# hd6303-exp-x1.net
KiCad netlist of a schematic drawn in EAGLE
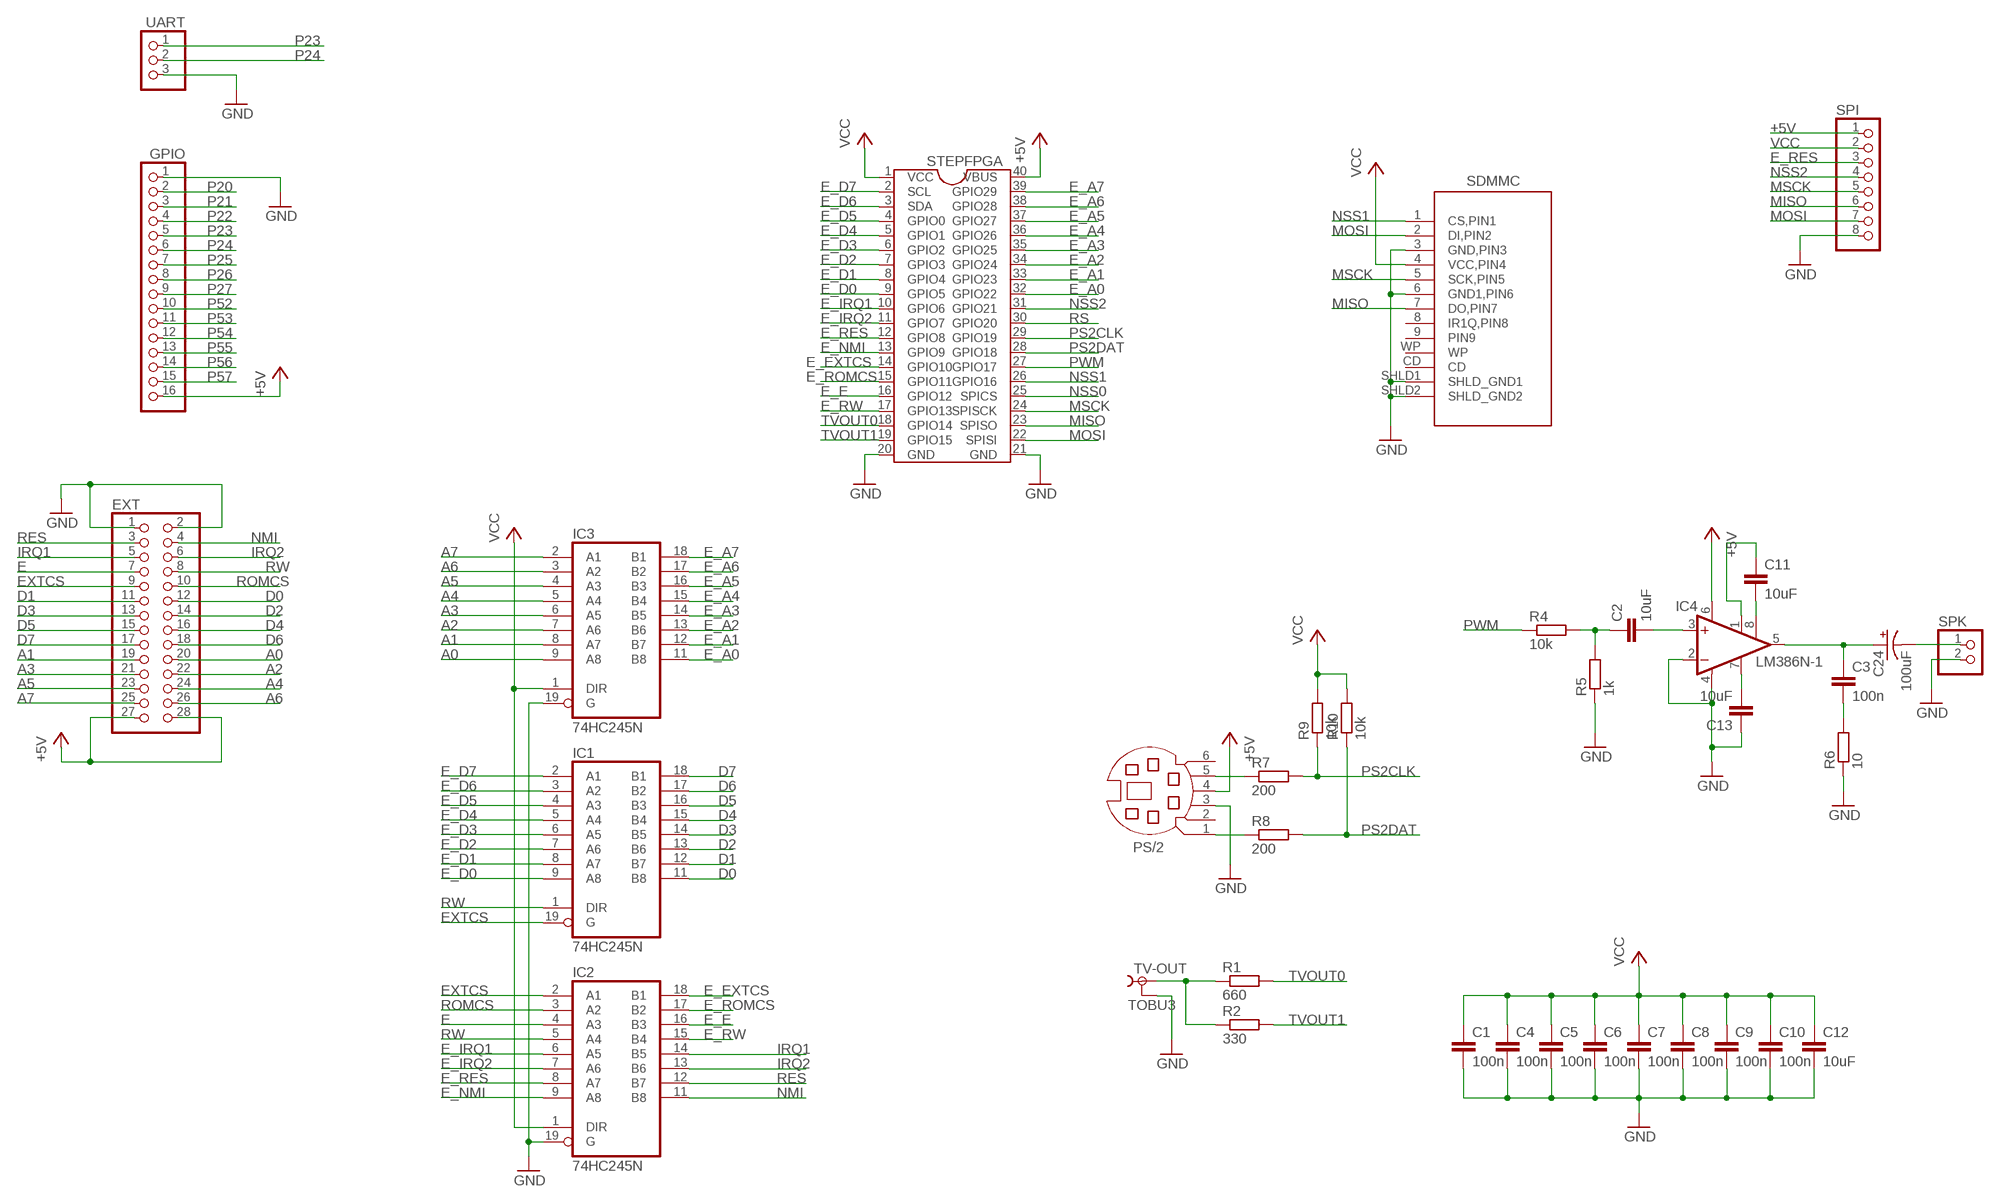
[diagram p0: schematic, sheet 1]
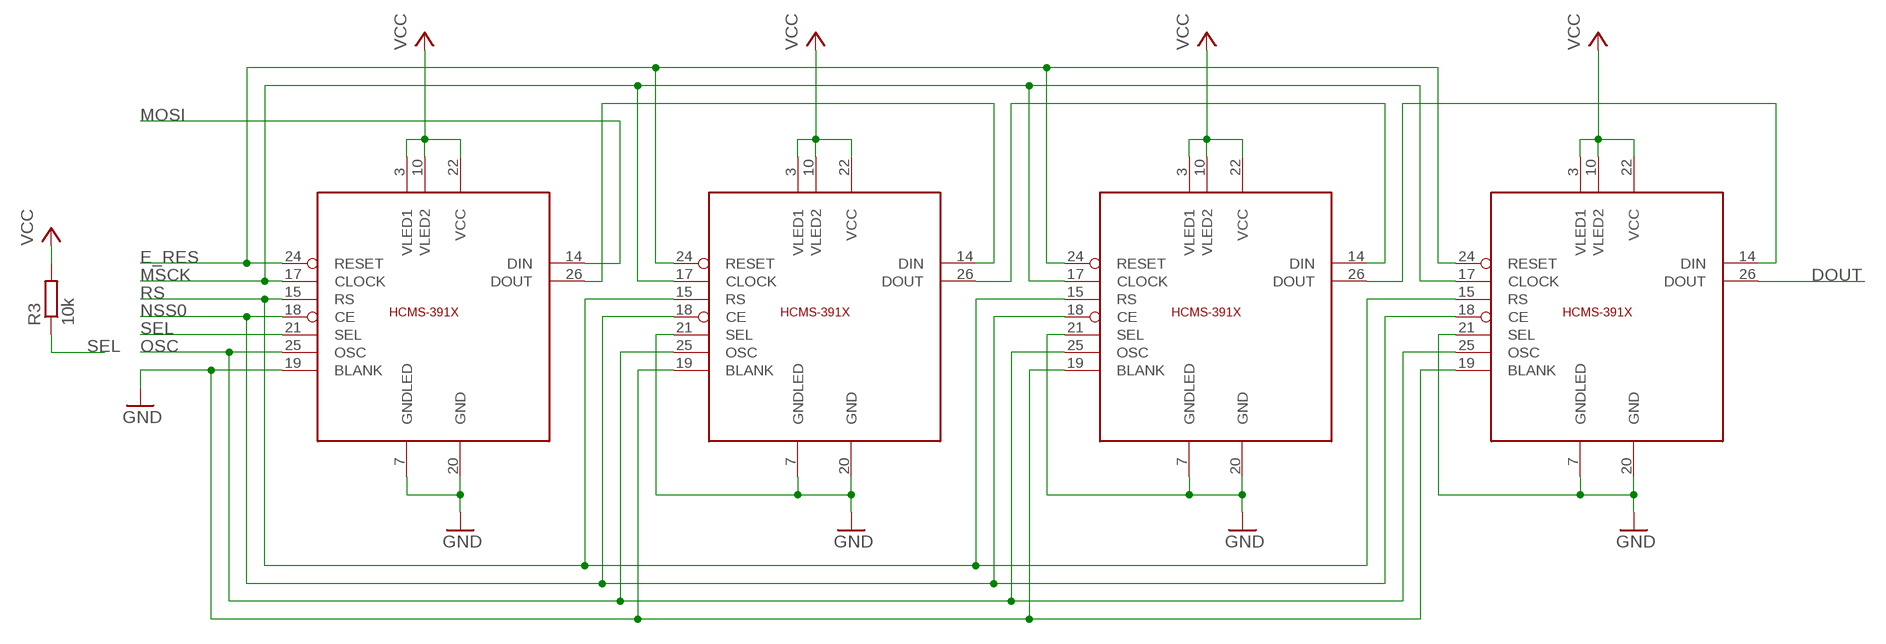
[diagram p1: schematic, sheet 2]

(export (version "E")
  (design (tool "Eeschema 10.0.6"))
  (components
    (comp (ref "R3")
      (value "10k")
      (footprint "eagle-import:R0603")
      (libsource (lib "eagle-import") (part "R-EU_R0603"))
    )
    (comp (ref "U$1")
      (value "HCMS-391X")
      (footprint "eagle-import:HCMS-391X")
      (libsource (lib "eagle-import") (part "HCMS-391X"))
    )
    (comp (ref "U$2")
      (value "HCMS-391X")
      (footprint "eagle-import:HCMS-391X")
      (libsource (lib "eagle-import") (part "HCMS-391X"))
    )
    (comp (ref "U$3")
      (value "HCMS-391X")
      (footprint "eagle-import:HCMS-391X")
      (libsource (lib "eagle-import") (part "HCMS-391X"))
    )
    (comp (ref "U$4")
      (value "HCMS-391X")
      (footprint "eagle-import:HCMS-391X")
      (libsource (lib "eagle-import") (part "HCMS-391X"))
    )
    (comp (ref "C1")
      (value "100n")
      (footprint "eagle-import:C0603")
      (libsource (lib "eagle-import") (part "C-EUC0603"))
    )
    (comp (ref "C2")
      (value "10uF")
      (footprint "eagle-import:C0805")
      (libsource (lib "eagle-import") (part "resistor_348_C-EUC0805"))
    )
    (comp (ref "C3")
      (value "100n")
      (footprint "eagle-import:C0603")
      (libsource (lib "eagle-import") (part "C-EUC0603"))
    )
    (comp (ref "C4")
      (value "100n")
      (footprint "eagle-import:C0603")
      (libsource (lib "eagle-import") (part "C-EUC0603"))
    )
    (comp (ref "C5")
      (value "100n")
      (footprint "eagle-import:C0603")
      (libsource (lib "eagle-import") (part "C-EUC0603"))
    )
    (comp (ref "C6")
      (value "100n")
      (footprint "eagle-import:C0603")
      (libsource (lib "eagle-import") (part "C-EUC0603"))
    )
    (comp (ref "C7")
      (value "100n")
      (footprint "eagle-import:C0603")
      (libsource (lib "eagle-import") (part "C-EUC0603"))
    )
    (comp (ref "C8")
      (value "100n")
      (footprint "eagle-import:C0603")
      (libsource (lib "eagle-import") (part "C-EUC0603"))
    )
    (comp (ref "C9")
      (value "100n")
      (footprint "eagle-import:C0603")
      (libsource (lib "eagle-import") (part "C-EUC0603"))
    )
    (comp (ref "C10")
      (value "100n")
      (footprint "eagle-import:C0603")
      (libsource (lib "eagle-import") (part "C-EUC0603"))
    )
    (comp (ref "C11")
      (value "10uF")
      (footprint "eagle-import:C0805")
      (libsource (lib "eagle-import") (part "resistor_348_C-EUC0805"))
    )
    (comp (ref "C12")
      (value "10uF")
      (footprint "eagle-import:C0805")
      (libsource (lib "eagle-import") (part "resistor_348_C-EUC0805"))
    )
    (comp (ref "C13")
      (value "10uF")
      (footprint "eagle-import:C0805")
      (libsource (lib "eagle-import") (part "resistor_348_C-EUC0805"))
    )
    (comp (ref "C24")
      (value "100uF")
      (footprint "eagle-import:EIA7343")
      (libsource (lib "eagle-import") (part "CAP_POL7343"))
    )
    (comp (ref "EXT")
      (value "PINHD-2X14")
      (footprint "eagle-import:2X14")
      (libsource (lib "eagle-import") (part "PINHD-2X14"))
    )
    (comp (ref "GPIO")
      (value "PINHD-1X16")
      (footprint "eagle-import:1X16")
      (libsource (lib "eagle-import") (part "PINHD-1X16"))
    )
    (comp (ref "IC1")
      (value "74HC245N")
      (footprint "eagle-import:DIL20")
      (libsource (lib "eagle-import") (part "74245NHC"))
    )
    (comp (ref "IC2")
      (value "74HC245N")
      (footprint "eagle-import:DIL20")
      (libsource (lib "eagle-import") (part "74245NHC"))
    )
    (comp (ref "IC3")
      (value "74HC245N")
      (footprint "eagle-import:DIL20")
      (libsource (lib "eagle-import") (part "74245NHC"))
    )
    (comp (ref "IC4")
      (value "LM386N-1")
      (footprint "eagle-import:DIL08")
      (libsource (lib "eagle-import") (part "LM386?-N1"))
    )
    (comp (ref "PS/2")
      (value "MD06SS")
      (footprint "eagle-import:MDIN06SS")
      (libsource (lib "eagle-import") (part "MD06SS"))
    )
    (comp (ref "R1")
      (value "660")
      (footprint "eagle-import:R0603")
      (libsource (lib "eagle-import") (part "R-EU_R0603"))
    )
    (comp (ref "R2")
      (value "330")
      (footprint "eagle-import:R0603")
      (libsource (lib "eagle-import") (part "R-EU_R0603"))
    )
    (comp (ref "R4")
      (value "10k")
      (footprint "eagle-import:R0603")
      (libsource (lib "eagle-import") (part "R-EU_R0603"))
    )
    (comp (ref "R5")
      (value "1k")
      (footprint "eagle-import:R0603")
      (libsource (lib "eagle-import") (part "R-EU_R0603"))
    )
    (comp (ref "R6")
      (value "10")
      (footprint "eagle-import:R0603")
      (libsource (lib "eagle-import") (part "R-EU_R0603"))
    )
    (comp (ref "R7")
      (value "200")
      (footprint "eagle-import:R0603")
      (libsource (lib "eagle-import") (part "R-EU_R0603"))
    )
    (comp (ref "R8")
      (value "200")
      (footprint "eagle-import:R0603")
      (libsource (lib "eagle-import") (part "R-EU_R0603"))
    )
    (comp (ref "R9")
      (value "10k")
      (footprint "eagle-import:R0603")
      (libsource (lib "eagle-import") (part "R-EU_R0603"))
    )
    (comp (ref "R10")
      (value "10k")
      (footprint "eagle-import:R0603")
      (libsource (lib "eagle-import") (part "R-EU_R0603"))
    )
    (comp (ref "SDMMC")
      (value "FCI_SD_SOCKET")
      (footprint "eagle-import:SD-MMC_SOCKET-PP")
      (fields (field (name "MF") "FCI") (field (name "MPN") "10067847-001RLF"))
      (libsource (lib "eagle-import") (part "FCI_SD_SOCKET"))
    )
    (comp (ref "SPI")
      (value "PINHD-1X8")
      (footprint "eagle-import:1X08")
      (libsource (lib "eagle-import") (part "PINHD-1X8"))
    )
    (comp (ref "SPK")
      (value "PINHD-1X2")
      (footprint "eagle-import:1X02")
      (libsource (lib "eagle-import") (part "PINHD-1X2"))
    )
    (comp (ref "STEPFPGA")
      (value "STEPFPGA")
      (footprint "eagle-import:DIL40")
      (libsource (lib "eagle-import") (part "STEPFPGA"))
    )
    (comp (ref "TV-OUT")
      (value "TOBU3")
      (footprint "eagle-import:TOBU3")
      (fields (field (name "MF") "FARNELL") (field (name "MPN") "TOBU 3"))
      (libsource (lib "eagle-import") (part "TOBU3"))
    )
    (comp (ref "UART")
      (value "PINHD-1X3")
      (footprint "eagle-import:1X03")
      (libsource (lib "eagle-import") (part "PINHD-1X3"))
    )
  )
  (nets
    (net (code "1") (name "+5V") (class "Default")
      (node (ref "EXT") (pin "27") (pinfunction "27_27") (pintype "passive"))
      (node (ref "EXT") (pin "28") (pinfunction "28_28") (pintype "passive"))
      (node (ref "GPIO") (pin "16") (pinfunction "16_16") (pintype "passive"))
      (node (ref "IC4") (pin "6") (pinfunction "VS_6") (pintype "power_in"))
      (node (ref "PS/2") (pin "4") (pinfunction "4_4") (pintype "passive"))
      (node (ref "SPI") (pin "1") (pinfunction "1_1") (pintype "passive"))
      (node (ref "STEPFPGA") (pin "40") (pinfunction "VBUS_40") (pintype "power_in"))
    )
    (net (code "2") (name "A0") (class "Default")
      (node (ref "EXT") (pin "20") (pinfunction "20_20") (pintype "passive"))
      (node (ref "IC3") (pin "9") (pinfunction "A8_9") (pintype "bidirectional"))
    )
    (net (code "3") (name "A1") (class "Default")
      (node (ref "EXT") (pin "19") (pinfunction "19_19") (pintype "passive"))
      (node (ref "IC3") (pin "8") (pinfunction "A7_8") (pintype "bidirectional"))
    )
    (net (code "4") (name "A2") (class "Default")
      (node (ref "EXT") (pin "22") (pinfunction "22_22") (pintype "passive"))
      (node (ref "IC3") (pin "7") (pinfunction "A6_7") (pintype "bidirectional"))
    )
    (net (code "5") (name "A3") (class "Default")
      (node (ref "EXT") (pin "21") (pinfunction "21_21") (pintype "passive"))
      (node (ref "IC3") (pin "6") (pinfunction "A5_6") (pintype "bidirectional"))
    )
    (net (code "6") (name "A4") (class "Default")
      (node (ref "EXT") (pin "24") (pinfunction "24_24") (pintype "passive"))
      (node (ref "IC3") (pin "5") (pinfunction "A4_5") (pintype "bidirectional"))
    )
    (net (code "7") (name "A5") (class "Default")
      (node (ref "EXT") (pin "23") (pinfunction "23_23") (pintype "passive"))
      (node (ref "IC3") (pin "4") (pinfunction "A3_4") (pintype "bidirectional"))
    )
    (net (code "8") (name "A6") (class "Default")
      (node (ref "EXT") (pin "26") (pinfunction "26_26") (pintype "passive"))
      (node (ref "IC3") (pin "3") (pinfunction "A2_3") (pintype "bidirectional"))
    )
    (net (code "9") (name "A7") (class "Default")
      (node (ref "EXT") (pin "25") (pinfunction "25_25") (pintype "passive"))
      (node (ref "IC3") (pin "2") (pinfunction "A1_2") (pintype "bidirectional"))
    )
    (net (code "10") (name "D0") (class "Default")
      (node (ref "EXT") (pin "12") (pinfunction "12_12") (pintype "passive"))
      (node (ref "IC1") (pin "11") (pinfunction "B8_11") (pintype "bidirectional"))
    )
    (net (code "11") (name "D1") (class "Default")
      (node (ref "EXT") (pin "11") (pinfunction "11_11") (pintype "passive"))
      (node (ref "IC1") (pin "12") (pinfunction "B7_12") (pintype "bidirectional"))
    )
    (net (code "12") (name "D2") (class "Default")
      (node (ref "EXT") (pin "14") (pinfunction "14_14") (pintype "passive"))
      (node (ref "IC1") (pin "13") (pinfunction "B6_13") (pintype "bidirectional"))
    )
    (net (code "13") (name "D3") (class "Default")
      (node (ref "EXT") (pin "13") (pinfunction "13_13") (pintype "passive"))
      (node (ref "IC1") (pin "14") (pinfunction "B5_14") (pintype "bidirectional"))
    )
    (net (code "14") (name "D4") (class "Default")
      (node (ref "EXT") (pin "16") (pinfunction "16_16") (pintype "passive"))
      (node (ref "IC1") (pin "15") (pinfunction "B4_15") (pintype "bidirectional"))
    )
    (net (code "15") (name "D5") (class "Default")
      (node (ref "EXT") (pin "15") (pinfunction "15_15") (pintype "passive"))
      (node (ref "IC1") (pin "16") (pinfunction "B3_16") (pintype "bidirectional"))
    )
    (net (code "16") (name "D6") (class "Default")
      (node (ref "EXT") (pin "18") (pinfunction "18_18") (pintype "passive"))
      (node (ref "IC1") (pin "17") (pinfunction "B2_17") (pintype "bidirectional"))
    )
    (net (code "17") (name "D7") (class "Default")
      (node (ref "EXT") (pin "17") (pinfunction "17_17") (pintype "passive"))
      (node (ref "IC1") (pin "18") (pinfunction "B1_18") (pintype "bidirectional"))
    )
    (net (code "18") (name "DOUT") (class "Default")
      (node (ref "U$4") (pin "26") (pinfunction "DOUT_26") (pintype "output"))
    )
    (net (code "19") (name "E") (class "Default")
      (node (ref "EXT") (pin "7") (pinfunction "7_7") (pintype "passive"))
      (node (ref "IC2") (pin "4") (pinfunction "A3_4") (pintype "bidirectional"))
    )
    (net (code "20") (name "EXTCS") (class "Default")
      (node (ref "EXT") (pin "9") (pinfunction "9_9") (pintype "passive"))
      (node (ref "IC1") (pin "19") (pinfunction "G_19") (pintype "input"))
      (node (ref "IC2") (pin "2") (pinfunction "A1_2") (pintype "bidirectional"))
    )
    (net (code "21") (name "E_A0") (class "Default")
      (node (ref "IC3") (pin "11") (pinfunction "B8_11") (pintype "bidirectional"))
      (node (ref "STEPFPGA") (pin "32") (pinfunction "GPIO22_32") (pintype "bidirectional"))
    )
    (net (code "22") (name "E_A1") (class "Default")
      (node (ref "IC3") (pin "12") (pinfunction "B7_12") (pintype "bidirectional"))
      (node (ref "STEPFPGA") (pin "33") (pinfunction "GPIO23_33") (pintype "bidirectional"))
    )
    (net (code "23") (name "E_A2") (class "Default")
      (node (ref "IC3") (pin "13") (pinfunction "B6_13") (pintype "bidirectional"))
      (node (ref "STEPFPGA") (pin "34") (pinfunction "GPIO24_34") (pintype "bidirectional"))
    )
    (net (code "24") (name "E_A3") (class "Default")
      (node (ref "IC3") (pin "14") (pinfunction "B5_14") (pintype "bidirectional"))
      (node (ref "STEPFPGA") (pin "35") (pinfunction "GPIO25_35") (pintype "bidirectional"))
    )
    (net (code "25") (name "E_A4") (class "Default")
      (node (ref "IC3") (pin "15") (pinfunction "B4_15") (pintype "bidirectional"))
      (node (ref "STEPFPGA") (pin "36") (pinfunction "GPIO26_36") (pintype "bidirectional"))
    )
    (net (code "26") (name "E_A5") (class "Default")
      (node (ref "IC3") (pin "16") (pinfunction "B3_16") (pintype "bidirectional"))
      (node (ref "STEPFPGA") (pin "37") (pinfunction "GPIO27_37") (pintype "bidirectional"))
    )
    (net (code "27") (name "E_A6") (class "Default")
      (node (ref "IC3") (pin "17") (pinfunction "B2_17") (pintype "bidirectional"))
      (node (ref "STEPFPGA") (pin "38") (pinfunction "GPIO28_38") (pintype "bidirectional"))
    )
    (net (code "28") (name "E_A7") (class "Default")
      (node (ref "IC3") (pin "18") (pinfunction "B1_18") (pintype "bidirectional"))
      (node (ref "STEPFPGA") (pin "39") (pinfunction "GPIO29_39") (pintype "bidirectional"))
    )
    (net (code "29") (name "E_D0") (class "Default")
      (node (ref "IC1") (pin "9") (pinfunction "A8_9") (pintype "bidirectional"))
      (node (ref "STEPFPGA") (pin "9") (pinfunction "GPIO5_9") (pintype "bidirectional"))
    )
    (net (code "30") (name "E_D1") (class "Default")
      (node (ref "IC1") (pin "8") (pinfunction "A7_8") (pintype "bidirectional"))
      (node (ref "STEPFPGA") (pin "8") (pinfunction "GPIO4_8") (pintype "bidirectional"))
    )
    (net (code "31") (name "E_D2") (class "Default")
      (node (ref "IC1") (pin "7") (pinfunction "A6_7") (pintype "bidirectional"))
      (node (ref "STEPFPGA") (pin "7") (pinfunction "GPIO3_7") (pintype "bidirectional"))
    )
    (net (code "32") (name "E_D3") (class "Default")
      (node (ref "IC1") (pin "6") (pinfunction "A5_6") (pintype "bidirectional"))
      (node (ref "STEPFPGA") (pin "6") (pinfunction "GPIO2_6") (pintype "bidirectional"))
    )
    (net (code "33") (name "E_D4") (class "Default")
      (node (ref "IC1") (pin "5") (pinfunction "A4_5") (pintype "bidirectional"))
      (node (ref "STEPFPGA") (pin "5") (pinfunction "GPIO1_5") (pintype "bidirectional"))
    )
    (net (code "34") (name "E_D5") (class "Default")
      (node (ref "IC1") (pin "4") (pinfunction "A3_4") (pintype "bidirectional"))
      (node (ref "STEPFPGA") (pin "4") (pinfunction "GPIO0_4") (pintype "bidirectional"))
    )
    (net (code "35") (name "E_D6") (class "Default")
      (node (ref "IC1") (pin "3") (pinfunction "A2_3") (pintype "bidirectional"))
      (node (ref "STEPFPGA") (pin "3") (pinfunction "SDA_3") (pintype "bidirectional"))
    )
    (net (code "36") (name "E_D7") (class "Default")
      (node (ref "IC1") (pin "2") (pinfunction "A1_2") (pintype "bidirectional"))
      (node (ref "STEPFPGA") (pin "2") (pinfunction "SCL_2") (pintype "bidirectional"))
    )
    (net (code "37") (name "E_E") (class "Default")
      (node (ref "IC2") (pin "16") (pinfunction "B3_16") (pintype "bidirectional"))
      (node (ref "STEPFPGA") (pin "16") (pinfunction "GPIO12_16") (pintype "bidirectional"))
    )
    (net (code "38") (name "E_EXTCS") (class "Default")
      (node (ref "IC2") (pin "18") (pinfunction "B1_18") (pintype "bidirectional"))
      (node (ref "STEPFPGA") (pin "14") (pinfunction "GPIO10_14") (pintype "bidirectional"))
    )
    (net (code "39") (name "E_IRQ1") (class "Default")
      (node (ref "IC2") (pin "6") (pinfunction "A5_6") (pintype "bidirectional"))
      (node (ref "STEPFPGA") (pin "10") (pinfunction "GPIO6_10") (pintype "bidirectional"))
    )
    (net (code "40") (name "E_IRQ2") (class "Default")
      (node (ref "IC2") (pin "7") (pinfunction "A6_7") (pintype "bidirectional"))
      (node (ref "STEPFPGA") (pin "11") (pinfunction "GPIO7_11") (pintype "bidirectional"))
    )
    (net (code "41") (name "E_NMI") (class "Default")
      (node (ref "IC2") (pin "9") (pinfunction "A8_9") (pintype "bidirectional"))
      (node (ref "STEPFPGA") (pin "13") (pinfunction "GPIO9_13") (pintype "bidirectional"))
    )
    (net (code "42") (name "E_RES") (class "Default")
      (node (ref "IC2") (pin "8") (pinfunction "A7_8") (pintype "bidirectional"))
      (node (ref "SPI") (pin "3") (pinfunction "3_3") (pintype "passive"))
      (node (ref "STEPFPGA") (pin "12") (pinfunction "GPIO8_12") (pintype "bidirectional"))
      (node (ref "U$1") (pin "24") (pinfunction "RESET_24") (pintype "input"))
      (node (ref "U$2") (pin "24") (pinfunction "RESET_24") (pintype "input"))
      (node (ref "U$3") (pin "24") (pinfunction "RESET_24") (pintype "input"))
      (node (ref "U$4") (pin "24") (pinfunction "RESET_24") (pintype "input"))
    )
    (net (code "43") (name "E_ROMCS") (class "Default")
      (node (ref "IC2") (pin "17") (pinfunction "B2_17") (pintype "bidirectional"))
      (node (ref "STEPFPGA") (pin "15") (pinfunction "GPIO11_15") (pintype "bidirectional"))
    )
    (net (code "44") (name "E_RW") (class "Default")
      (node (ref "IC2") (pin "15") (pinfunction "B4_15") (pintype "bidirectional"))
      (node (ref "STEPFPGA") (pin "17") (pinfunction "GPIO13_17") (pintype "bidirectional"))
    )
    (net (code "45") (name "GND") (class "Default")
      (node (ref "C1") (pin "2") (pinfunction "2_2") (pintype "passive"))
      (node (ref "C10") (pin "2") (pinfunction "2_2") (pintype "passive"))
      (node (ref "C12") (pin "2") (pinfunction "2_2") (pintype "passive"))
      (node (ref "C13") (pin "1") (pinfunction "1_1") (pintype "passive"))
      (node (ref "C4") (pin "2") (pinfunction "2_2") (pintype "passive"))
      (node (ref "C5") (pin "2") (pinfunction "2_2") (pintype "passive"))
      (node (ref "C6") (pin "2") (pinfunction "2_2") (pintype "passive"))
      (node (ref "C7") (pin "2") (pinfunction "2_2") (pintype "passive"))
      (node (ref "C8") (pin "2") (pinfunction "2_2") (pintype "passive"))
      (node (ref "C9") (pin "2") (pinfunction "2_2") (pintype "passive"))
      (node (ref "EXT") (pin "1") (pinfunction "1_1") (pintype "passive"))
      (node (ref "EXT") (pin "2") (pinfunction "2_2") (pintype "passive"))
      (node (ref "GPIO") (pin "1") (pinfunction "1_1") (pintype "passive"))
      (node (ref "IC2") (pin "19") (pinfunction "G_19") (pintype "input"))
      (node (ref "IC3") (pin "19") (pinfunction "G_19") (pintype "input"))
      (node (ref "IC4") (pin "2") (pinfunction "-IN_2") (pintype "input"))
      (node (ref "IC4") (pin "4") (pinfunction "GND_4") (pintype "power_in"))
      (node (ref "PS/2") (pin "3") (pinfunction "3_3") (pintype "passive"))
      (node (ref "R5") (pin "1") (pinfunction "1_1") (pintype "passive"))
      (node (ref "R6") (pin "1") (pinfunction "1_1") (pintype "passive"))
      (node (ref "SDMMC") (pin "3") (pinfunction "GND,PIN3_3") (pintype "bidirectional"))
      (node (ref "SDMMC") (pin "6") (pinfunction "GND1,PIN6_6") (pintype "bidirectional"))
      (node (ref "SDMMC") (pin "SHLD1") (pinfunction "SHLD_GND1_SHLD1") (pintype "bidirectional"))
      (node (ref "SDMMC") (pin "SHLD2") (pinfunction "SHLD_GND2_SHLD2") (pintype "bidirectional"))
      (node (ref "SPI") (pin "8") (pinfunction "8_8") (pintype "passive"))
      (node (ref "SPK") (pin "2") (pinfunction "2_2") (pintype "passive"))
      (node (ref "STEPFPGA") (pin "20") (pinfunction "GND_20") (pintype "power_in"))
      (node (ref "STEPFPGA") (pin "21") (pinfunction "GND_21") (pintype "power_in"))
      (node (ref "TV-OUT") (pin "2") (pinfunction "2_2") (pintype "passive"))
      (node (ref "TV-OUT") (pin "2@1") (pinfunction "2_2@1") (pintype "passive"))
      (node (ref "TV-OUT") (pin "2@2") (pinfunction "2_2@2") (pintype "passive"))
      (node (ref "U$1") (pin "19") (pinfunction "BLANK_19") (pintype "input"))
      (node (ref "U$1") (pin "20") (pinfunction "GND_20") (pintype "power_in"))
      (node (ref "U$1") (pin "7") (pinfunction "GNDLED_7") (pintype "power_in"))
      (node (ref "U$2") (pin "19") (pinfunction "BLANK_19") (pintype "input"))
      (node (ref "U$2") (pin "20") (pinfunction "GND_20") (pintype "power_in"))
      (node (ref "U$2") (pin "21") (pinfunction "SEL_21") (pintype "input"))
      (node (ref "U$2") (pin "7") (pinfunction "GNDLED_7") (pintype "power_in"))
      (node (ref "U$3") (pin "19") (pinfunction "BLANK_19") (pintype "input"))
      (node (ref "U$3") (pin "20") (pinfunction "GND_20") (pintype "power_in"))
      (node (ref "U$3") (pin "21") (pinfunction "SEL_21") (pintype "input"))
      (node (ref "U$3") (pin "7") (pinfunction "GNDLED_7") (pintype "power_in"))
      (node (ref "U$4") (pin "19") (pinfunction "BLANK_19") (pintype "input"))
      (node (ref "U$4") (pin "20") (pinfunction "GND_20") (pintype "power_in"))
      (node (ref "U$4") (pin "21") (pinfunction "SEL_21") (pintype "input"))
      (node (ref "U$4") (pin "7") (pinfunction "GNDLED_7") (pintype "power_in"))
      (node (ref "UART") (pin "3") (pinfunction "3_3") (pintype "passive"))
    )
    (net (code "46") (name "IRQ1") (class "Default")
      (node (ref "EXT") (pin "5") (pinfunction "5_5") (pintype "passive"))
      (node (ref "IC2") (pin "14") (pinfunction "B5_14") (pintype "bidirectional"))
    )
    (net (code "47") (name "IRQ2") (class "Default")
      (node (ref "EXT") (pin "6") (pinfunction "6_6") (pintype "passive"))
      (node (ref "IC2") (pin "13") (pinfunction "B6_13") (pintype "bidirectional"))
    )
    (net (code "48") (name "MISO") (class "Default")
      (node (ref "SDMMC") (pin "7") (pinfunction "DO,PIN7_7") (pintype "bidirectional"))
      (node (ref "SPI") (pin "6") (pinfunction "6_6") (pintype "passive"))
      (node (ref "STEPFPGA") (pin "23") (pinfunction "SPISO_23") (pintype "bidirectional"))
    )
    (net (code "49") (name "MOSI") (class "Default")
      (node (ref "SDMMC") (pin "2") (pinfunction "DI,PIN2_2") (pintype "bidirectional"))
      (node (ref "SPI") (pin "7") (pinfunction "7_7") (pintype "passive"))
      (node (ref "STEPFPGA") (pin "22") (pinfunction "SPISI_22") (pintype "bidirectional"))
      (node (ref "U$1") (pin "14") (pinfunction "DIN_14") (pintype "input"))
    )
    (net (code "50") (name "MSCK") (class "Default")
      (node (ref "SDMMC") (pin "5") (pinfunction "SCK,PIN5_5") (pintype "bidirectional"))
      (node (ref "SPI") (pin "5") (pinfunction "5_5") (pintype "passive"))
      (node (ref "STEPFPGA") (pin "24") (pinfunction "SPISCK_24") (pintype "bidirectional"))
      (node (ref "U$1") (pin "17") (pinfunction "CLOCK_17") (pintype "input"))
      (node (ref "U$2") (pin "17") (pinfunction "CLOCK_17") (pintype "input"))
      (node (ref "U$3") (pin "17") (pinfunction "CLOCK_17") (pintype "input"))
      (node (ref "U$4") (pin "17") (pinfunction "CLOCK_17") (pintype "input"))
    )
    (net (code "51") (name "NMI") (class "Default")
      (node (ref "EXT") (pin "4") (pinfunction "4_4") (pintype "passive"))
      (node (ref "IC2") (pin "11") (pinfunction "B8_11") (pintype "bidirectional"))
    )
    (net (code "52") (name "NSS0") (class "Default")
      (node (ref "STEPFPGA") (pin "25") (pinfunction "SPICS_25") (pintype "bidirectional"))
      (node (ref "U$1") (pin "18") (pinfunction "CE_18") (pintype "input"))
      (node (ref "U$2") (pin "18") (pinfunction "CE_18") (pintype "input"))
      (node (ref "U$3") (pin "18") (pinfunction "CE_18") (pintype "input"))
      (node (ref "U$4") (pin "18") (pinfunction "CE_18") (pintype "input"))
    )
    (net (code "53") (name "NSS1") (class "Default")
      (node (ref "SDMMC") (pin "1") (pinfunction "CS,PIN1_1") (pintype "bidirectional"))
      (node (ref "STEPFPGA") (pin "26") (pinfunction "GPIO16_26") (pintype "bidirectional"))
    )
    (net (code "54") (name "NSS2") (class "Default")
      (node (ref "SPI") (pin "4") (pinfunction "4_4") (pintype "passive"))
      (node (ref "STEPFPGA") (pin "31") (pinfunction "GPIO21_31") (pintype "bidirectional"))
    )
    (net (code "55") (name "Net-(C2-Pad1)") (class "Default")
      (node (ref "C2") (pin "1") (pinfunction "1_1") (pintype "passive"))
      (node (ref "R4") (pin "2") (pinfunction "2_2") (pintype "passive"))
      (node (ref "R5") (pin "2") (pinfunction "2_2") (pintype "passive"))
    )
    (net (code "56") (name "Net-(C3-Pad2)") (class "Default")
      (node (ref "C3") (pin "2") (pinfunction "2_2") (pintype "passive"))
      (node (ref "R6") (pin "2") (pinfunction "2_2") (pintype "passive"))
    )
    (net (code "57") (name "Net-(C11-Pad1)") (class "Default")
      (node (ref "C11") (pin "1") (pinfunction "1_1") (pintype "passive"))
      (node (ref "IC4") (pin "1") (pinfunction "GAIN_1") (pintype "passive"))
    )
    (net (code "58") (name "Net-(C11-Pad2)") (class "Default")
      (node (ref "C11") (pin "2") (pinfunction "2_2") (pintype "passive"))
      (node (ref "IC4") (pin "8") (pinfunction "GAIN_8") (pintype "passive"))
    )
    (net (code "59") (name "Net-(C24-+)") (class "Default")
      (node (ref "C24") (pin "A") (pinfunction "+_A") (pintype "passive"))
      (node (ref "C3") (pin "1") (pinfunction "1_1") (pintype "passive"))
      (node (ref "IC4") (pin "5") (pinfunction "OUT_5") (pintype "output"))
    )
    (net (code "60") (name "Net-(C24--)") (class "Default")
      (node (ref "C24") (pin "C") (pinfunction "-_C") (pintype "passive"))
      (node (ref "SPK") (pin "1") (pinfunction "1_1") (pintype "passive"))
    )
    (net (code "61") (name "Net-(IC4-+IN)") (class "Default")
      (node (ref "C2") (pin "2") (pinfunction "2_2") (pintype "passive"))
      (node (ref "IC4") (pin "3") (pinfunction "+IN_3") (pintype "input"))
    )
    (net (code "62") (name "Net-(IC4-BYPASS)") (class "Default")
      (node (ref "C13") (pin "2") (pinfunction "2_2") (pintype "passive"))
      (node (ref "IC4") (pin "7") (pinfunction "BYPASS_7") (pintype "passive"))
    )
    (net (code "63") (name "Net-(PS/2-Pad1)") (class "Default")
      (node (ref "PS/2") (pin "1") (pinfunction "1_1") (pintype "passive"))
      (node (ref "R8") (pin "1") (pinfunction "1_1") (pintype "passive"))
    )
    (net (code "64") (name "Net-(PS/2-Pad5)") (class "Default")
      (node (ref "PS/2") (pin "5") (pinfunction "5_5") (pintype "passive"))
      (node (ref "R7") (pin "1") (pinfunction "1_1") (pintype "passive"))
    )
    (net (code "65") (name "Net-(R1-Pad1)") (class "Default")
      (node (ref "R1") (pin "1") (pinfunction "1_1") (pintype "passive"))
      (node (ref "R2") (pin "1") (pinfunction "1_1") (pintype "passive"))
      (node (ref "TV-OUT") (pin "1") (pinfunction "1_1") (pintype "passive"))
    )
    (net (code "66") (name "Net-(U$1-DOUT)") (class "Default")
      (node (ref "U$1") (pin "26") (pinfunction "DOUT_26") (pintype "output"))
      (node (ref "U$2") (pin "14") (pinfunction "DIN_14") (pintype "input"))
    )
    (net (code "67") (name "Net-(U$2-DOUT)") (class "Default")
      (node (ref "U$2") (pin "26") (pinfunction "DOUT_26") (pintype "output"))
      (node (ref "U$3") (pin "14") (pinfunction "DIN_14") (pintype "input"))
    )
    (net (code "68") (name "Net-(U$3-DOUT)") (class "Default")
      (node (ref "U$3") (pin "26") (pinfunction "DOUT_26") (pintype "output"))
      (node (ref "U$4") (pin "14") (pinfunction "DIN_14") (pintype "input"))
    )
    (net (code "69") (name "OSC") (class "Default")
      (node (ref "U$1") (pin "25") (pinfunction "OSC_25") (pintype "bidirectional"))
      (node (ref "U$2") (pin "25") (pinfunction "OSC_25") (pintype "bidirectional"))
      (node (ref "U$3") (pin "25") (pinfunction "OSC_25") (pintype "bidirectional"))
      (node (ref "U$4") (pin "25") (pinfunction "OSC_25") (pintype "bidirectional"))
    )
    (net (code "70") (name "P20") (class "Default")
      (node (ref "GPIO") (pin "2") (pinfunction "2_2") (pintype "passive"))
    )
    (net (code "71") (name "P21") (class "Default")
      (node (ref "GPIO") (pin "3") (pinfunction "3_3") (pintype "passive"))
    )
    (net (code "72") (name "P22") (class "Default")
      (node (ref "GPIO") (pin "4") (pinfunction "4_4") (pintype "passive"))
    )
    (net (code "73") (name "P23") (class "Default")
      (node (ref "GPIO") (pin "5") (pinfunction "5_5") (pintype "passive"))
      (node (ref "UART") (pin "1") (pinfunction "1_1") (pintype "passive"))
    )
    (net (code "74") (name "P24") (class "Default")
      (node (ref "GPIO") (pin "6") (pinfunction "6_6") (pintype "passive"))
      (node (ref "UART") (pin "2") (pinfunction "2_2") (pintype "passive"))
    )
    (net (code "75") (name "P25") (class "Default")
      (node (ref "GPIO") (pin "7") (pinfunction "7_7") (pintype "passive"))
    )
    (net (code "76") (name "P26") (class "Default")
      (node (ref "GPIO") (pin "8") (pinfunction "8_8") (pintype "passive"))
    )
    (net (code "77") (name "P27") (class "Default")
      (node (ref "GPIO") (pin "9") (pinfunction "9_9") (pintype "passive"))
    )
    (net (code "78") (name "P52") (class "Default")
      (node (ref "GPIO") (pin "10") (pinfunction "10_10") (pintype "passive"))
    )
    (net (code "79") (name "P53") (class "Default")
      (node (ref "GPIO") (pin "11") (pinfunction "11_11") (pintype "passive"))
    )
    (net (code "80") (name "P54") (class "Default")
      (node (ref "GPIO") (pin "12") (pinfunction "12_12") (pintype "passive"))
    )
    (net (code "81") (name "P55") (class "Default")
      (node (ref "GPIO") (pin "13") (pinfunction "13_13") (pintype "passive"))
    )
    (net (code "82") (name "P56") (class "Default")
      (node (ref "GPIO") (pin "14") (pinfunction "14_14") (pintype "passive"))
    )
    (net (code "83") (name "P57") (class "Default")
      (node (ref "GPIO") (pin "15") (pinfunction "15_15") (pintype "passive"))
    )
    (net (code "84") (name "PS2CLK") (class "Default")
      (node (ref "R7") (pin "2") (pinfunction "2_2") (pintype "passive"))
      (node (ref "R9") (pin "1") (pinfunction "1_1") (pintype "passive"))
      (node (ref "STEPFPGA") (pin "29") (pinfunction "GPIO19_29") (pintype "bidirectional"))
    )
    (net (code "85") (name "PS2DAT") (class "Default")
      (node (ref "R10") (pin "1") (pinfunction "1_1") (pintype "passive"))
      (node (ref "R8") (pin "2") (pinfunction "2_2") (pintype "passive"))
      (node (ref "STEPFPGA") (pin "28") (pinfunction "GPIO18_28") (pintype "bidirectional"))
    )
    (net (code "86") (name "PWM") (class "Default")
      (node (ref "R4") (pin "1") (pinfunction "1_1") (pintype "passive"))
      (node (ref "STEPFPGA") (pin "27") (pinfunction "GPIO17_27") (pintype "bidirectional"))
    )
    (net (code "87") (name "RES") (class "Default")
      (node (ref "EXT") (pin "3") (pinfunction "3_3") (pintype "passive"))
      (node (ref "IC2") (pin "12") (pinfunction "B7_12") (pintype "bidirectional"))
    )
    (net (code "88") (name "ROMCS") (class "Default")
      (node (ref "EXT") (pin "10") (pinfunction "10_10") (pintype "passive"))
      (node (ref "IC2") (pin "3") (pinfunction "A2_3") (pintype "bidirectional"))
    )
    (net (code "89") (name "RS") (class "Default")
      (node (ref "STEPFPGA") (pin "30") (pinfunction "GPIO20_30") (pintype "bidirectional"))
      (node (ref "U$1") (pin "15") (pinfunction "RS_15") (pintype "input"))
      (node (ref "U$2") (pin "15") (pinfunction "RS_15") (pintype "input"))
      (node (ref "U$3") (pin "15") (pinfunction "RS_15") (pintype "input"))
      (node (ref "U$4") (pin "15") (pinfunction "RS_15") (pintype "input"))
    )
    (net (code "90") (name "RW") (class "Default")
      (node (ref "EXT") (pin "8") (pinfunction "8_8") (pintype "passive"))
      (node (ref "IC1") (pin "1") (pinfunction "DIR_1") (pintype "input"))
      (node (ref "IC2") (pin "5") (pinfunction "A4_5") (pintype "bidirectional"))
    )
    (net (code "91") (name "SEL") (class "Default")
      (node (ref "R3") (pin "1") (pinfunction "1_1") (pintype "passive"))
      (node (ref "U$1") (pin "21") (pinfunction "SEL_21") (pintype "input"))
    )
    (net (code "92") (name "TVOUT0") (class "Default")
      (node (ref "R1") (pin "2") (pinfunction "2_2") (pintype "passive"))
      (node (ref "STEPFPGA") (pin "18") (pinfunction "GPIO14_18") (pintype "bidirectional"))
    )
    (net (code "93") (name "TVOUT1") (class "Default")
      (node (ref "R2") (pin "2") (pinfunction "2_2") (pintype "passive"))
      (node (ref "STEPFPGA") (pin "19") (pinfunction "GPIO15_19") (pintype "bidirectional"))
    )
    (net (code "94") (name "VCC") (class "Default")
      (node (ref "C1") (pin "1") (pinfunction "1_1") (pintype "passive"))
      (node (ref "C10") (pin "1") (pinfunction "1_1") (pintype "passive"))
      (node (ref "C12") (pin "1") (pinfunction "1_1") (pintype "passive"))
      (node (ref "C4") (pin "1") (pinfunction "1_1") (pintype "passive"))
      (node (ref "C5") (pin "1") (pinfunction "1_1") (pintype "passive"))
      (node (ref "C6") (pin "1") (pinfunction "1_1") (pintype "passive"))
      (node (ref "C7") (pin "1") (pinfunction "1_1") (pintype "passive"))
      (node (ref "C8") (pin "1") (pinfunction "1_1") (pintype "passive"))
      (node (ref "C9") (pin "1") (pinfunction "1_1") (pintype "passive"))
      (node (ref "IC2") (pin "1") (pinfunction "DIR_1") (pintype "input"))
      (node (ref "IC3") (pin "1") (pinfunction "DIR_1") (pintype "input"))
      (node (ref "R10") (pin "2") (pinfunction "2_2") (pintype "passive"))
      (node (ref "R3") (pin "2") (pinfunction "2_2") (pintype "passive"))
      (node (ref "R9") (pin "2") (pinfunction "2_2") (pintype "passive"))
      (node (ref "SDMMC") (pin "4") (pinfunction "VCC,PIN4_4") (pintype "bidirectional"))
      (node (ref "SPI") (pin "2") (pinfunction "2_2") (pintype "passive"))
      (node (ref "STEPFPGA") (pin "1") (pinfunction "VCC_1") (pintype "power_in"))
      (node (ref "U$1") (pin "10") (pinfunction "VLED2_10") (pintype "power_in"))
      (node (ref "U$1") (pin "22") (pinfunction "VCC_22") (pintype "power_in"))
      (node (ref "U$1") (pin "3") (pinfunction "VLED1_3") (pintype "power_in"))
      (node (ref "U$2") (pin "10") (pinfunction "VLED2_10") (pintype "power_in"))
      (node (ref "U$2") (pin "22") (pinfunction "VCC_22") (pintype "power_in"))
      (node (ref "U$2") (pin "3") (pinfunction "VLED1_3") (pintype "power_in"))
      (node (ref "U$3") (pin "10") (pinfunction "VLED2_10") (pintype "power_in"))
      (node (ref "U$3") (pin "22") (pinfunction "VCC_22") (pintype "power_in"))
      (node (ref "U$3") (pin "3") (pinfunction "VLED1_3") (pintype "power_in"))
      (node (ref "U$4") (pin "10") (pinfunction "VLED2_10") (pintype "power_in"))
      (node (ref "U$4") (pin "22") (pinfunction "VCC_22") (pintype "power_in"))
      (node (ref "U$4") (pin "3") (pinfunction "VLED1_3") (pintype "power_in"))
    )
    (net (code "95") (name "unconnected-(PS/2-Pad2)") (class "Default")
      (node (ref "PS/2") (pin "2") (pinfunction "2_2") (pintype "passive"))
    )
    (net (code "96") (name "unconnected-(PS/2-Pad6)") (class "Default")
      (node (ref "PS/2") (pin "6") (pinfunction "6_6") (pintype "passive"))
    )
    (net (code "97") (name "unconnected-(SDMMC-IR1Q,PIN8-Pad8)") (class "Default")
      (node (ref "SDMMC") (pin "8") (pinfunction "IR1Q,PIN8_8") (pintype "bidirectional"))
    )
    (net (code "98") (name "unconnected-(SDMMC-PIN9-Pad9)") (class "Default")
      (node (ref "SDMMC") (pin "9") (pinfunction "PIN9_9") (pintype "bidirectional"))
    )
    (net (code "99") (name "unconnected-(SDMMC-PadCD)") (class "Default")
      (node (ref "SDMMC") (pin "CD") (pinfunction "CD_CD") (pintype "bidirectional"))
    )
    (net (code "100") (name "unconnected-(SDMMC-PadWP)") (class "Default")
      (node (ref "SDMMC") (pin "WP") (pinfunction "WP_WP") (pintype "bidirectional"))
    )
  )
)
